# CPU.net
KiCad netlist of a schematic drawn in Altium Designer
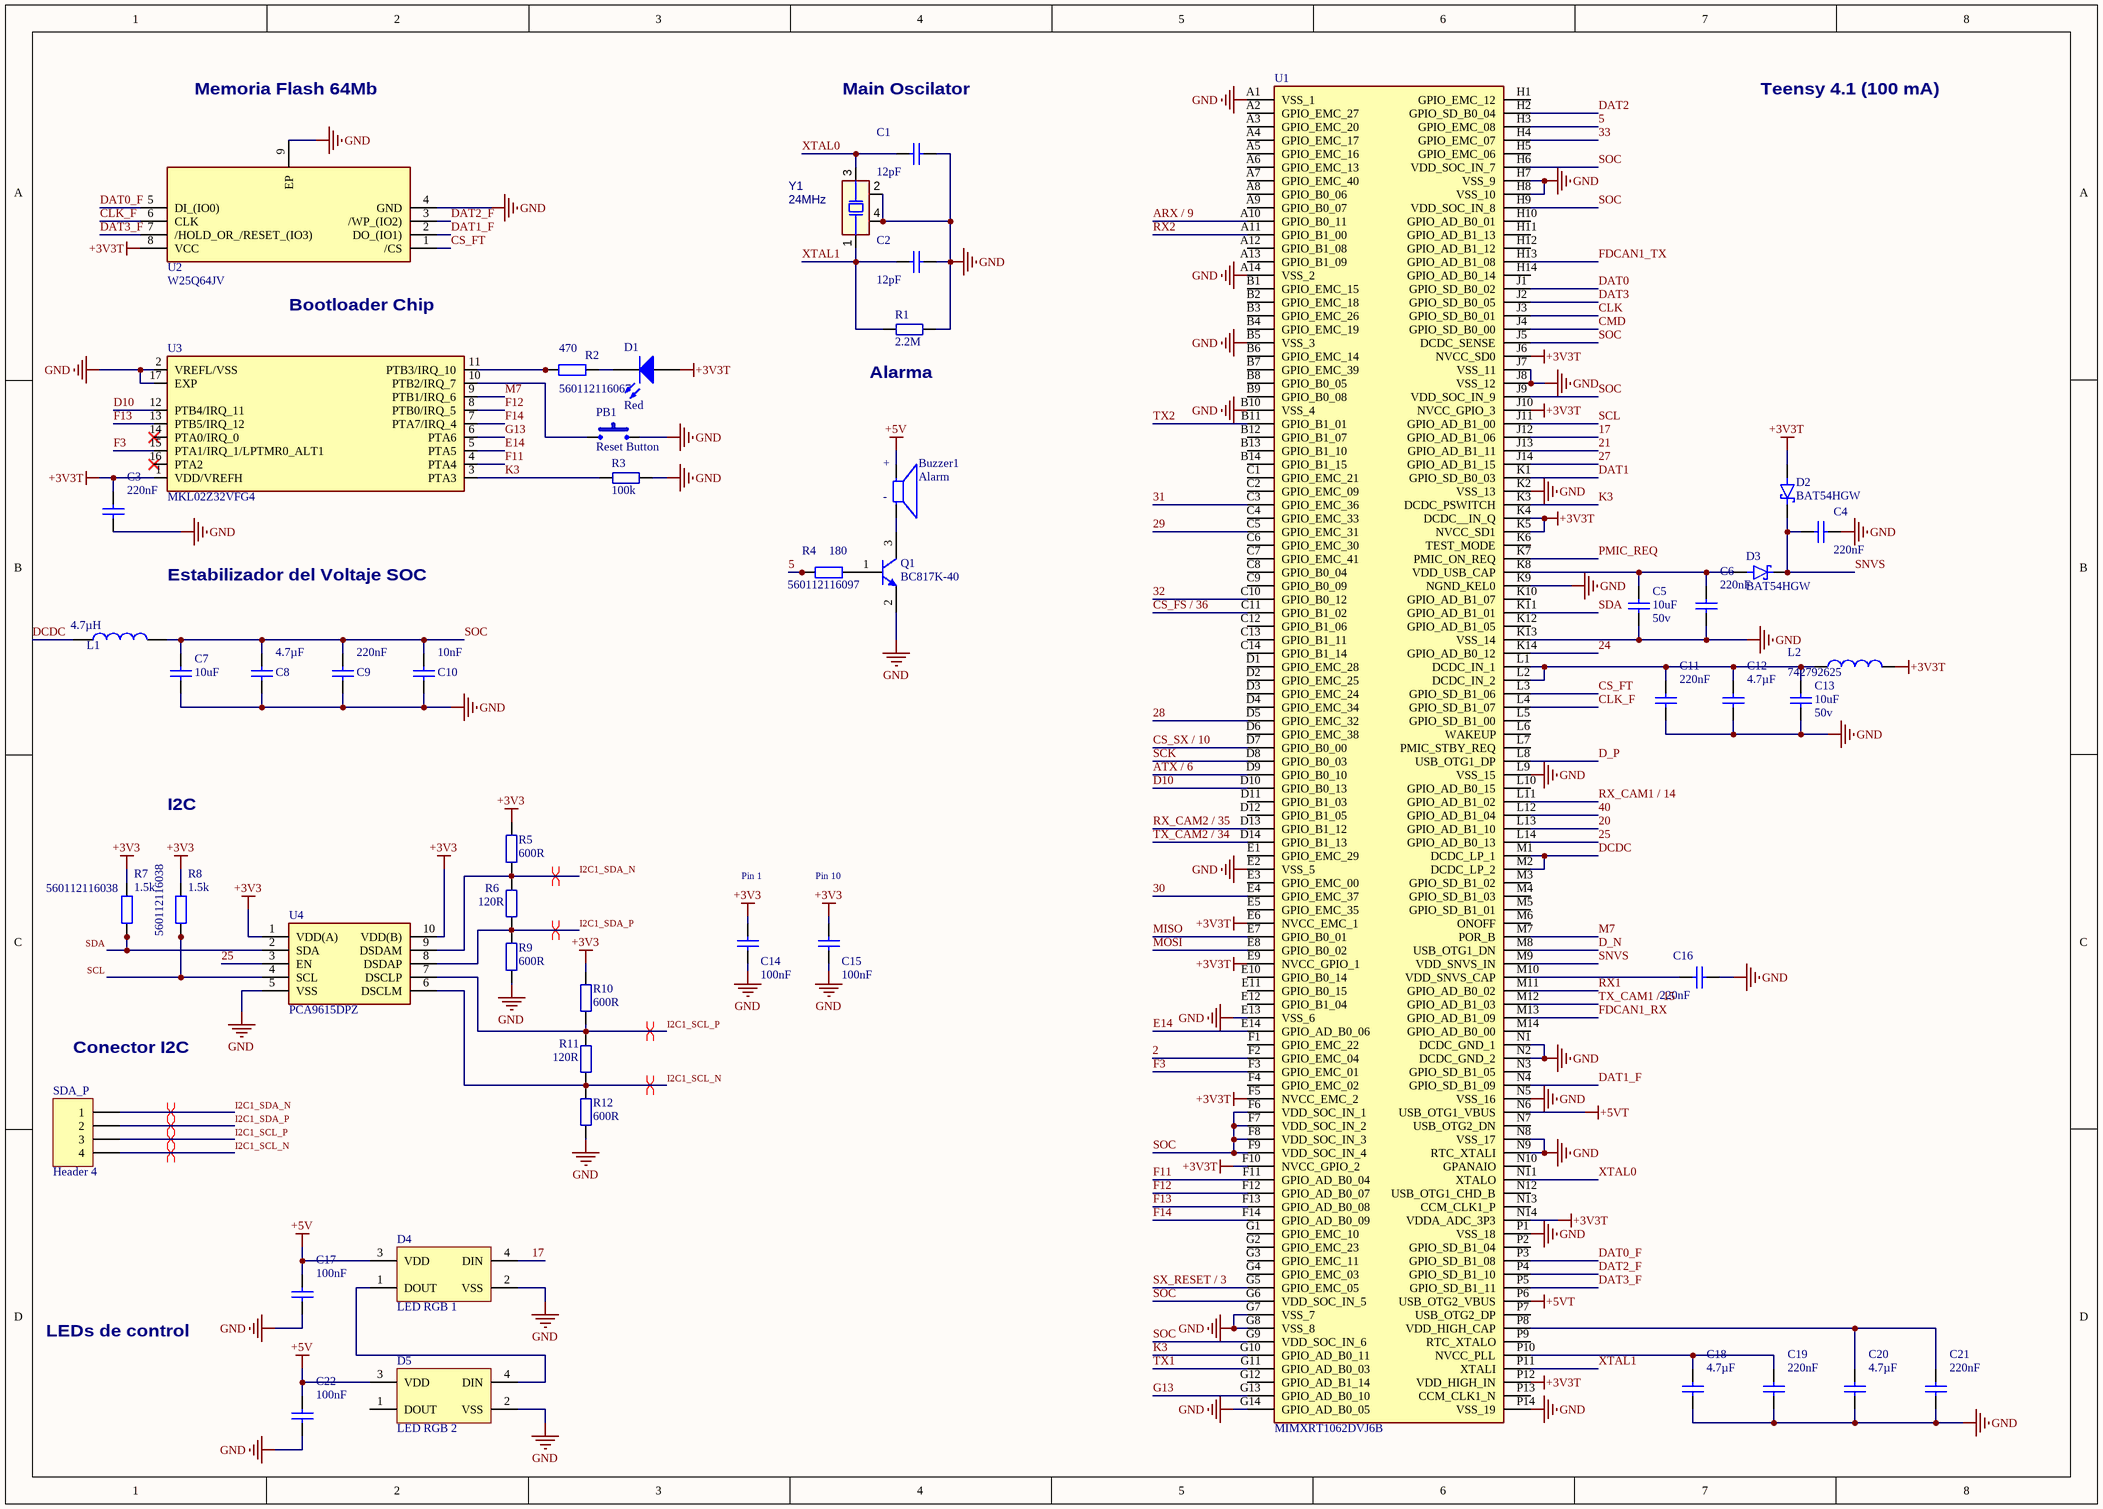
[diagram p0:  CPU.SchDoc]

(export (version "E")
  (design (tool "Eeschema 10.0.6"))
  (components
    (comp (ref "Buzzer1")
      (value "Alarm")
      (footprint "CMT-8504-100-SMT-TR-Footprint-1")
      (libsource (lib "LEEM UPM") (part "CMT-8504-100"))
    )
    (comp (ref "C1")
      (value "12pF")
      (footprint "WCAP-CSRF_0402")
      (description "WCAP-CSRF Multilayer Ceramic Chip Capacitor High Frequency, size 0402, NP0 Class I, 12pF, 50VDC")
      (fields
        (field (name "MANUFACTURER PART NUMBER") "885392005127")
        (field (name "MANUFACTURER") "Wurth Elektronik")
      )
      (libsource (lib "LEEM UPM") (part "885392005147"))
    )
    (comp (ref "C2")
      (value "12pF")
      (footprint "WCAP-CSRF_0402")
      (description "WCAP-CSRF Multilayer Ceramic Chip Capacitor High Frequency, size 0402, NP0 Class I, 12pF, 50VDC")
      (fields
        (field (name "MANUFACTURER PART NUMBER") "885392005127")
        (field (name "MANUFACTURER") "Wurth Elektronik")
      )
      (libsource (lib "LEEM UPM") (part "885392005147"))
    )
    (comp (ref "C3")
      (value "220nF")
      (footprint "WCAP-CSGP_0603_L1.6W0.8H0.8_Reflow")
      (description "WCAP-CSGP Multilayer Ceramic Chip Capacitor, General Purpose, size 0603, X7R, 220nF, 25VDC")
      (fields
        (field (name "MANUFACTURER PART NUMBER") "885012206073")
        (field (name "MANUFACTURER") "Wurth Elektronik")
      )
      (libsource (lib "LEEM UPM") (part "885012209047R"))
    )
    (comp (ref "C4")
      (value "220nF")
      (footprint "WCAP-CSGP_0603_L1.6W0.8H0.8_Reflow")
      (description "WCAP-CSGP Multilayer Ceramic Chip Capacitor, General Purpose, size 0603, X7R, 220nF, 25VDC")
      (fields
        (field (name "MANUFACTURER PART NUMBER") "885012206073")
        (field (name "MANUFACTURER") "Wurth Elektronik")
      )
      (libsource (lib "LEEM UPM") (part "885012209047R"))
    )
    (comp (ref "C5")
      (value "10uF")
      (footprint "MY_0603")
      (description "None polar capacitor")
      (fields
        (field (name "ASID PART NUMBER") "C-AS")
        (field (name "VOLTE") "50v")
        (field (name "Comment") "Cap ceramic")
      )
      (libsource (lib "LEEM UPM") (part "Cap ceramic"))
    )
    (comp (ref "C6")
      (value "220nF")
      (footprint "WCAP-CSGP_0603_L1.6W0.8H0.8_Reflow")
      (description "WCAP-CSGP Multilayer Ceramic Chip Capacitor, General Purpose, size 0603, X7R, 220nF, 25VDC")
      (fields
        (field (name "MANUFACTURER PART NUMBER") "885012206073")
        (field (name "MANUFACTURER") "Wurth Elektronik")
      )
      (libsource (lib "LEEM UPM") (part "885012209047R"))
    )
    (comp (ref "C7")
      (value "10uF")
      (footprint "MY_0603")
      (description "None polar capacitor")
      (fields (field (name "ASID PART NUMBER") "C-AS") (field (name "Comment") "Cap ceramic"))
      (libsource (lib "LEEM UPM") (part "Cap ceramic"))
    )
    (comp (ref "C8")
      (value "4.7µF")
      (footprint "WCAP-CSGP_0603_L1.6W0.8H0.8_Reflow")
      (description "WCAP-CSGP Multilayer Ceramic Chip Capacitor, General Purpose, size 0603, X5R, 4.7uF, 10VDC")
      (fields
        (field (name "MANUFACTURER PART NUMBER") "885012106012")
        (field (name "MANUFACTURER") "Wurth Elektronik")
      )
      (libsource (lib "LEEM UPM") (part "885012209047R"))
    )
    (comp (ref "C9")
      (value "220nF")
      (footprint "WCAP-CSGP_0603_L1.6W0.8H0.8_Reflow")
      (description "WCAP-CSGP Multilayer Ceramic Chip Capacitor, General Purpose, size 0603, X7R, 220nF, 25VDC")
      (fields
        (field (name "MANUFACTURER PART NUMBER") "885012206073")
        (field (name "MANUFACTURER") "Wurth Elektronik")
      )
      (libsource (lib "LEEM UPM") (part "885012209047R"))
    )
    (comp (ref "C10")
      (value "10nF")
      (footprint "WCAP-CSGP_0603_L1.6W0.8H0.8_Reflow")
      (description "WCAP-CSGP Multilayer Ceramic Chip Capacitor, General Purpose, size 0603, X7R, 10nF, 25VDC")
      (fields
        (field (name "MANUFACTURER") "Wurth Elektronik")
        (field (name "MANUFACTURER PART NUMBER") "885012206065")
      )
      (libsource (lib "LEEM UPM") (part "885012209047R"))
    )
    (comp (ref "C11")
      (value "220nF")
      (footprint "WCAP-CSGP_0603_L1.6W0.8H0.8_Reflow")
      (description "WCAP-CSGP Multilayer Ceramic Chip Capacitor, General Purpose, size 0603, X7R, 220nF, 25VDC")
      (fields
        (field (name "MANUFACTURER PART NUMBER") "885012206073")
        (field (name "MANUFACTURER") "Wurth Elektronik")
      )
      (libsource (lib "LEEM UPM") (part "885012209047R"))
    )
    (comp (ref "C12")
      (value "4.7µF")
      (footprint "WCAP-CSGP_0603_L1.6W0.8H0.8_Reflow")
      (description "WCAP-CSGP Multilayer Ceramic Chip Capacitor, General Purpose, size 0603, X5R, 4.7uF, 10VDC")
      (fields
        (field (name "MANUFACTURER PART NUMBER") "885012106012")
        (field (name "MANUFACTURER") "Wurth Elektronik")
      )
      (libsource (lib "LEEM UPM") (part "885012209047R"))
    )
    (comp (ref "C13")
      (value "10uF")
      (footprint "MY_0603")
      (description "None polar capacitor")
      (fields
        (field (name "ASID PART NUMBER") "C-AS")
        (field (name "VOLTE") "50v")
        (field (name "Comment") "Cap ceramic")
      )
      (libsource (lib "LEEM UPM") (part "Cap ceramic"))
    )
    (comp (ref "C14")
      (value "100nF")
      (footprint "WCAP-CSGP_0603_L1.6W0.8H0.8_Reflow")
      (description "WCAP-CSGP Multilayer Ceramic Chip Capacitor, General Purpose, size 0603, X7R, 100nF, 25VDC")
      (fields
        (field (name "MANUFACTURER") "Wurth Elektronik")
        (field (name "MANUFACTURER PART NUMBER") "885012206071")
      )
      (libsource (lib "LEEM UPM") (part "885012209047R"))
    )
    (comp (ref "C15")
      (value "100nF")
      (footprint "WCAP-CSGP_0603_L1.6W0.8H0.8_Reflow")
      (description "WCAP-CSGP Multilayer Ceramic Chip Capacitor, General Purpose, size 0603, X7R, 100nF, 25VDC")
      (fields
        (field (name "MANUFACTURER") "Wurth Elektronik")
        (field (name "MANUFACTURER PART NUMBER") "885012206071")
      )
      (libsource (lib "LEEM UPM") (part "885012209047R"))
    )
    (comp (ref "C16")
      (value "220nF")
      (footprint "WCAP-CSGP_0603_L1.6W0.8H0.8_Reflow")
      (description "WCAP-CSGP Multilayer Ceramic Chip Capacitor, General Purpose, size 0603, X7R, 220nF, 25VDC")
      (fields
        (field (name "MANUFACTURER PART NUMBER") "885012206073")
        (field (name "MANUFACTURER") "Wurth Elektronik")
      )
      (libsource (lib "LEEM UPM") (part "885012209047R"))
    )
    (comp (ref "C17")
      (value "100nF")
      (footprint "WCAP-CSGP_0603_L1.6W0.8H0.8_Reflow")
      (description "WCAP-CSGP Multilayer Ceramic Chip Capacitor, General Purpose, size 0603, X7R, 100nF, 25VDC")
      (fields
        (field (name "MANUFACTURER") "Wurth Elektronik")
        (field (name "MANUFACTURER PART NUMBER") "885012206071")
      )
      (libsource (lib "LEEM UPM") (part "885012209047R"))
    )
    (comp (ref "C18")
      (value "4.7µF")
      (footprint "WCAP-CSGP_0603_L1.6W0.8H0.8_Reflow")
      (description "WCAP-CSGP Multilayer Ceramic Chip Capacitor, General Purpose, size 0603, X5R, 4.7uF, 10VDC")
      (fields
        (field (name "MANUFACTURER PART NUMBER") "885012106012")
        (field (name "MANUFACTURER") "Wurth Elektronik")
      )
      (libsource (lib "LEEM UPM") (part "885012209047R"))
    )
    (comp (ref "C19")
      (value "220nF")
      (footprint "WCAP-CSGP_0603_L1.6W0.8H0.8_Reflow")
      (description "WCAP-CSGP Multilayer Ceramic Chip Capacitor, General Purpose, size 0603, X7R, 220nF, 25VDC")
      (fields
        (field (name "MANUFACTURER PART NUMBER") "885012206073")
        (field (name "MANUFACTURER") "Wurth Elektronik")
      )
      (libsource (lib "LEEM UPM") (part "885012209047R"))
    )
    (comp (ref "C20")
      (value "4.7µF")
      (footprint "WCAP-CSGP_0603_L1.6W0.8H0.8_Reflow")
      (description "WCAP-CSGP Multilayer Ceramic Chip Capacitor, General Purpose, size 0603, X5R, 4.7uF, 10VDC")
      (fields
        (field (name "MANUFACTURER PART NUMBER") "885012106012")
        (field (name "MANUFACTURER") "Wurth Elektronik")
      )
      (libsource (lib "LEEM UPM") (part "885012209047R"))
    )
    (comp (ref "C21")
      (value "220nF")
      (footprint "WCAP-CSGP_0603_L1.6W0.8H0.8_Reflow")
      (description "WCAP-CSGP Multilayer Ceramic Chip Capacitor, General Purpose, size 0603, X7R, 220nF, 25VDC")
      (fields
        (field (name "MANUFACTURER PART NUMBER") "885012206073")
        (field (name "MANUFACTURER") "Wurth Elektronik")
      )
      (libsource (lib "LEEM UPM") (part "885012209047R"))
    )
    (comp (ref "C22")
      (value "100nF")
      (footprint "WCAP-CSGP_0603_L1.6W0.8H0.8_Reflow")
      (description "WCAP-CSGP Multilayer Ceramic Chip Capacitor, General Purpose, size 0603, X7R, 100nF, 25VDC")
      (fields
        (field (name "MANUFACTURER") "Wurth Elektronik")
        (field (name "MANUFACTURER PART NUMBER") "885012206071")
      )
      (libsource (lib "LEEM UPM") (part "885012209047R"))
    )
    (comp (ref "D1")
      (value "Red")
      (footprint "MY_LED_0805")
      (description "Typical INFRARED GaAs LED")
      (fields (field (name "ASID PART NUMBER") "LED-AS"))
      (libsource (lib "Mylib+Rev+4") (part "LED"))
    )
    (comp (ref "D2")
      (value "BAT54HGW")
      (footprint "BAT54HGW-Footprint-1")
      (description "BAT54HGW Schotty Diode")
      (libsource (lib "LEEM UPM") (part "BAT54HGW"))
    )
    (comp (ref "D3")
      (value "BAT54HGW")
      (footprint "BAT54HGW-Footprint-1")
      (description "BAT54HGW Schotty Diode")
      (libsource (lib "LEEM UPM") (part "BAT54HGW"))
    )
    (comp (ref "D4")
      (value "LED RGB 1")
      (footprint "1313210530000")
      (description "WL-ICLED Integrated Controller within LED, Side View 3210, 5.5mA")
      (fields
        (field (name "MANUFACTURER") "Wurth Elektronik")
        (field (name "MANUFACTURER PART NUMBER") "1313210530000")
      )
      (libsource (lib "LEEM UPM") (part "1313210530000"))
    )
    (comp (ref "D5")
      (value "LED RGB 2")
      (footprint "1313210530000")
      (description "WL-ICLED Integrated Controller within LED, Side View 3210, 5.5mA")
      (fields
        (field (name "MANUFACTURER") "Wurth Elektronik")
        (field (name "MANUFACTURER PART NUMBER") "1313210530000")
      )
      (libsource (lib "LEEM UPM") (part "1313210530000"))
    )
    (comp (ref "L1")
      (value "74479775247")
      (footprint "WE-PMI_0805_L2W1.2H1")
      (description "WE-PMI SMT Power Multilayer Inductor, size 0805, 4.7µH, 0.85A, 312.5mO")
      (fields (field (name "INDUCTANCE") "4.7µH") (field (name "MANUFACTURER") "Wurth Elektronik"))
      (libsource (lib "LEEM UPM") (part "74479887310A"))
    )
    (comp (ref "L2")
      (value "742792625")
      (footprint "WE-CBF_0603_L1.6W0.8H0.8_HC")
      (description "WE-CBF SMT EMI Suppression Ferrite Bead, size 0603, 120Ohm, 2A")
      (fields (field (name "MANUFACTURER") "Wurth Elektronik"))
      (libsource (lib "LEEM UPM") (part "7427928801"))
    )
    (comp (ref "PB1")
      (value "Reset Button")
      (footprint "Push Button-Footprint-1")
      (description "Push Button")
      (fields (field (name "SOURCE") "IFS_Altium.SchLib"))
      (libsource (lib "LEEM UPM") (part "Push Button"))
    )
    (comp (ref "Q1")
      (value "BC817K-40")
      (footprint "INF-SOT23_N")
      (description "Trans GP BJT NPN 45V 0.5A 500mW Automotive 3-Pin SOT-23 T/R")
      (libsource (lib "LEEM UPM") (part "INF-BJTNPN-BEC-3"))
    )
    (comp (ref "R1")
      (value "2.2M")
      (footprint "R0603-0.45")
      (description "Resistor, generic")
      (libsource (lib "IFS_Altium") (part "R"))
    )
    (comp (ref "R2")
      (value "560112116067")
      (footprint "WRIS-RSKS_0603_Reflow")
      (description "WRIS-RSKS Thick Film Resistor, size 0603, 470Ohm, 100mW")
      (fields (field (name "MANUFACTURER") "Wurth Elektronik") (field (name "ALTIUM_VALUE") "470"))
      (libsource (lib "LEEM UPM") (part "560112140010"))
    )
    (comp (ref "R3")
      (value "100k")
      (footprint "R0603-0.45")
      (description "Resistor, generic")
      (libsource (lib "IFS_Altium") (part "R"))
    )
    (comp (ref "R4")
      (value "560112116097")
      (footprint "WRIS-RSKS_0603_Reflow")
      (description "WRIS-RSKS Thick Film Resistor, size 0603, 180Ohm, 100mW")
      (fields (field (name "ALTIUM_VALUE") "180") (field (name "MANUFACTURER") "Wurth Elektronik"))
      (libsource (lib "") (part "560112140010_2"))
    )
    (comp (ref "R5")
      (value "600R")
      (footprint "R0603-0.45")
      (description "Resistor, 600R, 0805, 0.5W")
      (fields
        (field (name "MANUFACTURER") "Vishay")
        (field (name "MANUFACTURER PART NUMBER") "CRCW0805600RFKEAHP")
      )
      (libsource (lib "LEEM UPM") (part "RK73H2ALTD1004F"))
    )
    (comp (ref "R6")
      (value "120R")
      (footprint "R0603-0.45")
      (description "Resistor, 120R, 0805, 0.5W")
      (fields
        (field (name "MANUFACTURER") "Panasonic")
        (field (name "MANUFACTURER PART NUMBER") "ERJ-P06F1200V")
      )
      (libsource (lib "LEEM UPM") (part "RK73H2ALTD1004F"))
    )
    (comp (ref "R7")
      (value "560112116038")
      (footprint "WRIS-RSKS_0603_Reflow")
      (description "WRIS-RSKS Thick Film Resistor, size 0603, 1500Ohm, 100mW")
      (fields (field (name "ALTIUM_VALUE") "1.5k") (field (name "MANUFACTURER") "Wurth Elektronik"))
      (libsource (lib "") (part "560112140010_1"))
    )
    (comp (ref "R8")
      (value "560112116038")
      (footprint "WRIS-RSKS_0603_Reflow")
      (description "WRIS-RSKS Thick Film Resistor, size 0603, 1500Ohm, 100mW")
      (fields (field (name "ALTIUM_VALUE") "1.5k") (field (name "MANUFACTURER") "Wurth Elektronik"))
      (libsource (lib "") (part "560112140010_1"))
    )
    (comp (ref "R9")
      (value "600R")
      (footprint "R0603-0.45")
      (description "Resistor, 600R, 0805, 0.5W")
      (fields
        (field (name "MANUFACTURER") "Vishay")
        (field (name "MANUFACTURER PART NUMBER") "CRCW0805600RFKEAHP")
      )
      (libsource (lib "LEEM UPM") (part "RK73H2ALTD1004F"))
    )
    (comp (ref "R10")
      (value "600R")
      (footprint "R0603-0.45")
      (description "Resistor, 600R, 0805, 0.5W")
      (fields
        (field (name "MANUFACTURER") "Vishay")
        (field (name "MANUFACTURER PART NUMBER") "CRCW0805600RFKEAHP")
      )
      (libsource (lib "LEEM UPM") (part "RK73H2ALTD1004F"))
    )
    (comp (ref "R11")
      (value "120R")
      (footprint "R0603-0.45")
      (description "Resistor, generic")
      (fields
        (field (name "MANUFACTURER") "Panasonic")
        (field (name "MANUFACTURER PART NUMBER") "ERJ-P06F1200V")
      )
      (libsource (lib "LEEM UPM") (part "RK73H2ALTD1004F"))
    )
    (comp (ref "R12")
      (value "600R")
      (footprint "R0603-0.45")
      (description "Resistor, 600R, 0805, 0.5W")
      (fields
        (field (name "MANUFACTURER") "Vishay")
        (field (name "MANUFACTURER PART NUMBER") "CRCW0805600RFKEAHP")
      )
      (libsource (lib "LEEM UPM") (part "RK73H2ALTD1004F"))
    )
    (comp (ref "SDA_P")
      (value "Header 4")
      (footprint "JST XH")
      (description "Header, 4-Pin")
      (fields (field (name "ASID PART NUMBER") "Header 4-AS"))
      (libsource (lib "LEEM UPM") (part "Header 4"))
    )
    (comp (ref "U1")
      (value "MIMXRT1062DVJ6B")
      (footprint "BGA196C80P14X14_1200X1200X152")
      (description "IC MCU 32BIT EXT MEM 196MAPBGA")
      (fields (field (name "MOUSER PART NUMBER") "771-MIMXRT1062DVJ6B"))
      (libsource (lib "LEEM UPM") (part "MIMXRT1062DVJ6B"))
    )
    (comp (ref "U2")
      (value "W25Q64JV")
      (footprint "WSON 8X6")
      (description "NOR Flash spiFlash, 64M-bit, DTR, 4Kb Uniform Sector")
      (fields
        (field (name "ARROW PART NUMBER") "W25Q64JVXGIM TR")
        (field (name "MOUSER PART NUMBER") "454-W25Q64JVXGIMTR")
      )
      (libsource (lib "LEEM UPM") (part "W25Q64JV"))
    )
    (comp (ref "U3")
      (value "MKL02Z32VFG4")
      (footprint "QFN50P300X300X65-17N")
      (description "ARMÂ®CortexÂ®-M0+ Kinetis KL02å¾®æŽ§åˆ¶å™¨IC 32ä½48MHz 32KBï¼ˆ32K x 8ï¼‰é—ªå­˜16-QFNï¼ˆ3x3ï¼‰")
      (fields (field (name "MF") "NXP USA"))
      (libsource (lib "LEEM UPM") (part "MKL02Z32VFG4"))
    )
    (comp (ref "U4")
      (value "PCA9615DPZ")
      (footprint "PCA9615DPZ-Footprint-1")
      (description "2 Channel  I2C-busbuffer")
      (fields (field (name "MANUFACTURER") "NXP Semiconductors"))
      (libsource (lib "LEEM UPM") (part "PCA9615DPZ-Symbol-1"))
    )
    (comp (ref "Y1")
      (value "24MHz")
      (footprint "EPSON-FA-128_V")
      (description "Crystal, 24 MHz, +/- 10 ppm, -20 to 75 degC, 4-Pin SMD, RoHS, Tape and Reel")
      (libsource (lib "LEEM UPM") (part "CMP-00014-7"))
    )
  )
  (nets
    (net (code "1") (name "+3V3") (class "Default")
      (node (ref "C14") (pin "2") (pinfunction "2_2") (pintype "passive"))
      (node (ref "C15") (pin "2") (pinfunction "2_2") (pintype "passive"))
      (node (ref "R10") (pin "1") (pinfunction "1_1") (pintype "passive"))
      (node (ref "R5") (pin "1") (pinfunction "1_1") (pintype "passive"))
      (node (ref "R7") (pin "1") (pinfunction "1_1") (pintype "passive"))
      (node (ref "R8") (pin "1") (pinfunction "1_1") (pintype "passive"))
      (node (ref "U4") (pin "1") (pinfunction "VDD(A)_1") (pintype "passive"))
      (node (ref "U4") (pin "10") (pinfunction "VDD(B)_10") (pintype "passive"))
    )
    (net (code "2") (name "+3V3T") (class "Default")
      (node (ref "C3") (pin "1") (pinfunction "1_1") (pintype "passive"))
      (node (ref "D1") (pin "A") (pinfunction "A_A") (pintype "passive"))
      (node (ref "D2") (pin "A") (pinfunction "A_A") (pintype "passive"))
      (node (ref "L2") (pin "2") (pinfunction "2_2") (pintype "passive"))
      (node (ref "U1") (pin "E6") (pinfunction "NVCC_EMC_1_E6") (pintype "passive"))
      (node (ref "U1") (pin "E9") (pinfunction "NVCC_GPIO_1_E9") (pintype "passive"))
      (node (ref "U1") (pin "F10") (pinfunction "NVCC_GPIO_2_F10") (pintype "passive"))
      (node (ref "U1") (pin "F5") (pinfunction "NVCC_EMC_2_F5") (pintype "passive"))
      (node (ref "U1") (pin "J10") (pinfunction "NVCC_GPIO_3_J10") (pintype "passive"))
      (node (ref "U1") (pin "J6") (pinfunction "NVCC_SD0_J6") (pintype "passive"))
      (node (ref "U1") (pin "K4") (pinfunction "DCDC__IN_Q_K4") (pintype "passive"))
      (node (ref "U1") (pin "K5") (pinfunction "NVCC_SD1_K5") (pintype "passive"))
      (node (ref "U1") (pin "N14") (pinfunction "VDDA_ADC_3P3_N14") (pintype "passive"))
      (node (ref "U1") (pin "P12") (pinfunction "VDD_HIGH_IN_P12") (pintype "passive"))
      (node (ref "U2") (pin "8") (pinfunction "VCC_8") (pintype "passive"))
      (node (ref "U3") (pin "1") (pinfunction "VDD/VREFH_1") (pintype "power_in"))
    )
    (net (code "3") (name "+5V") (class "Default")
      (node (ref "Buzzer1") (pin "P") (pinfunction "P_P") (pintype "passive"))
      (node (ref "C17") (pin "1") (pinfunction "1_1") (pintype "passive"))
      (node (ref "C22") (pin "1") (pinfunction "1_1") (pintype "passive"))
      (node (ref "D4") (pin "3") (pinfunction "VDD_3") (pintype "passive"))
      (node (ref "D5") (pin "3") (pinfunction "VDD_3") (pintype "passive"))
    )
    (net (code "4") (name "+5VT") (class "Default")
      (node (ref "U1") (pin "N6") (pinfunction "USB_OTG1_VBUS_N6") (pintype "passive"))
      (node (ref "U1") (pin "P6") (pinfunction "USB_OTG2_VBUS_P6") (pintype "passive"))
    )
    (net (code "5") (name "/2") (class "Default")
      (node (ref "U1") (pin "F2") (pinfunction "GPIO_EMC_04_F2") (pintype "passive"))
    )
    (net (code "6") (name "/5") (class "Default")
      (node (ref "R4") (pin "1") (pinfunction "1_1") (pintype "passive"))
      (node (ref "U1") (pin "H3") (pinfunction "GPIO_EMC_08_H3") (pintype "passive"))
    )
    (net (code "7") (name "/17") (class "Default")
      (node (ref "D4") (pin "4") (pinfunction "DIN_4") (pintype "passive"))
      (node (ref "U1") (pin "J12") (pinfunction "GPIO_AD_B1_06_J12") (pintype "passive"))
    )
    (net (code "8") (name "/20") (class "Default")
      (node (ref "U1") (pin "L13") (pinfunction "GPIO_AD_B1_10_L13") (pintype "passive"))
    )
    (net (code "9") (name "/21") (class "Default")
      (node (ref "U1") (pin "J13") (pinfunction "GPIO_AD_B1_11_J13") (pintype "passive"))
    )
    (net (code "10") (name "/24") (class "Default")
      (node (ref "U1") (pin "K14") (pinfunction "GPIO_AD_B0_12_K14") (pintype "passive"))
    )
    (net (code "11") (name "/25") (class "Default")
      (node (ref "U1") (pin "L14") (pinfunction "GPIO_AD_B0_13_L14") (pintype "passive"))
      (node (ref "U4") (pin "3") (pinfunction "EN_3") (pintype "passive"))
    )
    (net (code "12") (name "/27") (class "Default")
      (node (ref "U1") (pin "J14") (pinfunction "GPIO_AD_B1_15_J14") (pintype "passive"))
    )
    (net (code "13") (name "/28") (class "Default")
      (node (ref "U1") (pin "D5") (pinfunction "GPIO_EMC_32_D5") (pintype "passive"))
    )
    (net (code "14") (name "/29") (class "Default")
      (node (ref "U1") (pin "C5") (pinfunction "GPIO_EMC_31_C5") (pintype "passive"))
    )
    (net (code "15") (name "/30") (class "Default")
      (node (ref "U1") (pin "E4") (pinfunction "GPIO_EMC_37_E4") (pintype "passive"))
    )
    (net (code "16") (name "/31") (class "Default")
      (node (ref "U1") (pin "C3") (pinfunction "GPIO_EMC_36_C3") (pintype "passive"))
    )
    (net (code "17") (name "/32") (class "Default")
      (node (ref "U1") (pin "C10") (pinfunction "GPIO_B0_12_C10") (pintype "passive"))
    )
    (net (code "18") (name "/33") (class "Default")
      (node (ref "U1") (pin "H4") (pinfunction "GPIO_EMC_07_H4") (pintype "passive"))
    )
    (net (code "19") (name "/40") (class "Default")
      (node (ref "U1") (pin "L12") (pinfunction "GPIO_AD_B1_04_L12") (pintype "passive"))
    )
    (net (code "20") (name "/ARX {slash} 9") (class "Default")
      (node (ref "U1") (pin "A10") (pinfunction "GPIO_B0_11_A10") (pintype "passive"))
    )
    (net (code "21") (name "/ATX {slash} 6") (class "Default")
      (node (ref "U1") (pin "D9") (pinfunction "GPIO_B0_10_D9") (pintype "passive"))
    )
    (net (code "22") (name "/CLK") (class "Default")
      (node (ref "U1") (pin "J3") (pinfunction "GPIO_SD_B0_01_J3") (pintype "passive"))
    )
    (net (code "23") (name "/CLK_F") (class "Default")
      (node (ref "U1") (pin "L4") (pinfunction "GPIO_SD_B1_07_L4") (pintype "passive"))
      (node (ref "U2") (pin "6") (pinfunction "CLK_6") (pintype "passive"))
    )
    (net (code "24") (name "/CMD") (class "Default")
      (node (ref "U1") (pin "J4") (pinfunction "GPIO_SD_B0_00_J4") (pintype "passive"))
    )
    (net (code "25") (name "/CS_FS {slash} 36") (class "Default")
      (node (ref "U1") (pin "C11") (pinfunction "GPIO_B1_02_C11") (pintype "passive"))
    )
    (net (code "26") (name "/CS_FT") (class "Default")
      (node (ref "U1") (pin "L3") (pinfunction "GPIO_SD_B1_06_L3") (pintype "passive"))
      (node (ref "U2") (pin "1") (pinfunction "/CS_1") (pintype "passive"))
    )
    (net (code "27") (name "/CS_SX {slash} 10") (class "Default")
      (node (ref "U1") (pin "D7") (pinfunction "GPIO_B0_00_D7") (pintype "passive"))
    )
    (net (code "28") (name "/D10") (class "Default")
      (node (ref "U1") (pin "D10") (pinfunction "GPIO_B0_13_D10") (pintype "passive"))
      (node (ref "U3") (pin "12") (pinfunction "PTB4/IRQ_11_12") (pintype "bidirectional"))
    )
    (net (code "29") (name "/DAT0") (class "Default")
      (node (ref "U1") (pin "J1") (pinfunction "GPIO_SD_B0_02_J1") (pintype "passive"))
    )
    (net (code "30") (name "/DAT0_F") (class "Default")
      (node (ref "U1") (pin "P3") (pinfunction "GPIO_SD_B1_08_P3") (pintype "passive"))
      (node (ref "U2") (pin "5") (pinfunction "DI_(IO0)_5") (pintype "passive"))
    )
    (net (code "31") (name "/DAT1") (class "Default")
      (node (ref "U1") (pin "K1") (pinfunction "GPIO_SD_B0_03_K1") (pintype "passive"))
    )
    (net (code "32") (name "/DAT1_F") (class "Default")
      (node (ref "U1") (pin "N4") (pinfunction "GPIO_SD_B1_09_N4") (pintype "passive"))
      (node (ref "U2") (pin "2") (pinfunction "DO_(IO1)_2") (pintype "passive"))
    )
    (net (code "33") (name "/DAT2") (class "Default")
      (node (ref "U1") (pin "H2") (pinfunction "GPIO_SD_B0_04_H2") (pintype "passive"))
    )
    (net (code "34") (name "/DAT2_F") (class "Default")
      (node (ref "U1") (pin "P4") (pinfunction "GPIO_SD_B1_10_P4") (pintype "passive"))
      (node (ref "U2") (pin "3") (pinfunction "/WP_(IO2)_3") (pintype "passive"))
    )
    (net (code "35") (name "/DAT3") (class "Default")
      (node (ref "U1") (pin "J2") (pinfunction "GPIO_SD_B0_05_J2") (pintype "passive"))
    )
    (net (code "36") (name "/DAT3_F") (class "Default")
      (node (ref "U1") (pin "P5") (pinfunction "GPIO_SD_B1_11_P5") (pintype "passive"))
      (node (ref "U2") (pin "7") (pinfunction "/HOLD_OR_/RESET_(IO3)_7") (pintype "passive"))
    )
    (net (code "37") (name "/DCDC") (class "Default")
      (node (ref "L1") (pin "1") (pinfunction "1_1") (pintype "passive"))
      (node (ref "U1") (pin "M1") (pinfunction "DCDC_LP_1_M1") (pintype "passive"))
      (node (ref "U1") (pin "M2") (pinfunction "DCDC_LP_2_M2") (pintype "passive"))
    )
    (net (code "38") (name "/D_N") (class "Default")
      (node (ref "U1") (pin "M8") (pinfunction "USB_OTG1_DN_M8") (pintype "passive"))
    )
    (net (code "39") (name "/D_P") (class "Default")
      (node (ref "U1") (pin "L8") (pinfunction "USB_OTG1_DP_L8") (pintype "passive"))
    )
    (net (code "40") (name "/E14") (class "Default")
      (node (ref "U1") (pin "E14") (pinfunction "GPIO_AD_B0_06_E14") (pintype "passive"))
      (node (ref "U3") (pin "5") (pinfunction "PTA5_5") (pintype "bidirectional"))
    )
    (net (code "41") (name "/F3") (class "Default")
      (node (ref "U1") (pin "F3") (pinfunction "GPIO_EMC_01_F3") (pintype "passive"))
      (node (ref "U3") (pin "15") (pinfunction "PTA1/IRQ_1/LPTMR0_ALT1_15") (pintype "bidirectional"))
    )
    (net (code "42") (name "/F11") (class "Default")
      (node (ref "U1") (pin "F11") (pinfunction "GPIO_AD_B0_04_F11") (pintype "passive"))
      (node (ref "U3") (pin "4") (pinfunction "PTA4_4") (pintype "bidirectional"))
    )
    (net (code "43") (name "/F12") (class "Default")
      (node (ref "U1") (pin "F12") (pinfunction "GPIO_AD_B0_07_F12") (pintype "passive"))
      (node (ref "U3") (pin "8") (pinfunction "PTB0/IRQ_5_8") (pintype "bidirectional"))
    )
    (net (code "44") (name "/F13") (class "Default")
      (node (ref "U1") (pin "F13") (pinfunction "GPIO_AD_B0_08_F13") (pintype "passive"))
      (node (ref "U3") (pin "13") (pinfunction "PTB5/IRQ_12_13") (pintype "bidirectional"))
    )
    (net (code "45") (name "/F14") (class "Default")
      (node (ref "U1") (pin "F14") (pinfunction "GPIO_AD_B0_09_F14") (pintype "passive"))
      (node (ref "U3") (pin "7") (pinfunction "PTA7/IRQ_4_7") (pintype "bidirectional"))
    )
    (net (code "46") (name "/FDCAN1_RX") (class "Default")
      (node (ref "U1") (pin "M13") (pinfunction "GPIO_AD_B1_09_M13") (pintype "passive"))
    )
    (net (code "47") (name "/FDCAN1_TX") (class "Default")
      (node (ref "U1") (pin "H13") (pinfunction "GPIO_AD_B1_08_H13") (pintype "passive"))
    )
    (net (code "48") (name "/G13") (class "Default")
      (node (ref "U1") (pin "G13") (pinfunction "GPIO_AD_B0_10_G13") (pintype "passive"))
      (node (ref "U3") (pin "6") (pinfunction "PTA6_6") (pintype "bidirectional"))
    )
    (net (code "49") (name "/I2C1_SCL_N") (class "Default")
      (node (ref "R11") (pin "1") (pinfunction "1_1") (pintype "passive"))
      (node (ref "R12") (pin "1") (pinfunction "1_1") (pintype "passive"))
      (node (ref "SDA_P") (pin "4") (pinfunction "4_4") (pintype "passive"))
      (node (ref "U4") (pin "6") (pinfunction "DSCLM_6") (pintype "passive"))
    )
    (net (code "50") (name "/I2C1_SCL_P") (class "Default")
      (node (ref "R10") (pin "2") (pinfunction "2_2") (pintype "passive"))
      (node (ref "R11") (pin "2") (pinfunction "2_2") (pintype "passive"))
      (node (ref "SDA_P") (pin "3") (pinfunction "3_3") (pintype "passive"))
      (node (ref "U4") (pin "7") (pinfunction "DSCLP_7") (pintype "passive"))
    )
    (net (code "51") (name "/I2C1_SDA_N") (class "Default")
      (node (ref "R5") (pin "2") (pinfunction "2_2") (pintype "passive"))
      (node (ref "R6") (pin "2") (pinfunction "2_2") (pintype "passive"))
      (node (ref "SDA_P") (pin "1") (pinfunction "1_1") (pintype "passive"))
      (node (ref "U4") (pin "9") (pinfunction "DSDAM_9") (pintype "passive"))
    )
    (net (code "52") (name "/I2C1_SDA_P") (class "Default")
      (node (ref "R6") (pin "1") (pinfunction "1_1") (pintype "passive"))
      (node (ref "R9") (pin "1") (pinfunction "1_1") (pintype "passive"))
      (node (ref "SDA_P") (pin "2") (pinfunction "2_2") (pintype "passive"))
      (node (ref "U4") (pin "8") (pinfunction "DSDAP_8") (pintype "passive"))
    )
    (net (code "53") (name "/K3") (class "Default")
      (node (ref "R3") (pin "1") (pinfunction "1_1") (pintype "passive"))
      (node (ref "U1") (pin "G10") (pinfunction "GPIO_AD_B0_11_G10") (pintype "passive"))
      (node (ref "U1") (pin "K3") (pinfunction "DCDC_PSWITCH_K3") (pintype "passive"))
      (node (ref "U3") (pin "3") (pinfunction "PTA3_3") (pintype "bidirectional"))
    )
    (net (code "54") (name "/M7") (class "Default")
      (node (ref "U1") (pin "M7") (pinfunction "POR_B_M7") (pintype "passive"))
      (node (ref "U3") (pin "9") (pinfunction "PTB1/IRQ_6_9") (pintype "bidirectional"))
    )
    (net (code "55") (name "/MISO") (class "Default")
      (node (ref "U1") (pin "E7") (pinfunction "GPIO_B0_01_E7") (pintype "passive"))
    )
    (net (code "56") (name "/MOSI") (class "Default")
      (node (ref "U1") (pin "E8") (pinfunction "GPIO_B0_02_E8") (pintype "passive"))
    )
    (net (code "57") (name "/PMIC_REQ") (class "Default")
      (node (ref "U1") (pin "K7") (pinfunction "PMIC_ON_REQ_K7") (pintype "passive"))
    )
    (net (code "58") (name "/RX1") (class "Default")
      (node (ref "U1") (pin "M11") (pinfunction "GPIO_AD_B0_02_M11") (pintype "passive"))
    )
    (net (code "59") (name "/RX2") (class "Default")
      (node (ref "U1") (pin "A11") (pinfunction "GPIO_B1_00_A11") (pintype "passive"))
    )
    (net (code "60") (name "/RX_CAM1 {slash} 14") (class "Default")
      (node (ref "U1") (pin "L11") (pinfunction "GPIO_AD_B1_02_L11") (pintype "passive"))
    )
    (net (code "61") (name "/RX_CAM2 {slash} 35") (class "Default")
      (node (ref "U1") (pin "D13") (pinfunction "GPIO_B1_12_D13") (pintype "passive"))
    )
    (net (code "62") (name "/SCK") (class "Default")
      (node (ref "U1") (pin "D8") (pinfunction "GPIO_B0_03_D8") (pintype "passive"))
    )
    (net (code "63") (name "/SCL") (class "Default")
      (node (ref "R8") (pin "2") (pinfunction "2_2") (pintype "passive"))
      (node (ref "U1") (pin "J11") (pinfunction "GPIO_AD_B1_00_J11") (pintype "passive"))
      (node (ref "U4") (pin "4") (pinfunction "SCL_4") (pintype "passive"))
    )
    (net (code "64") (name "/SDA") (class "Default")
      (node (ref "R7") (pin "2") (pinfunction "2_2") (pintype "passive"))
      (node (ref "U1") (pin "K11") (pinfunction "GPIO_AD_B1_01_K11") (pintype "passive"))
      (node (ref "U4") (pin "2") (pinfunction "SDA_2") (pintype "passive"))
    )
    (net (code "65") (name "/SNVS") (class "Default")
      (node (ref "C4") (pin "2") (pinfunction "2_2") (pintype "passive"))
      (node (ref "D2") (pin "C") (pinfunction "K_C") (pintype "passive"))
      (node (ref "D3") (pin "C") (pinfunction "K_C") (pintype "passive"))
      (node (ref "U1") (pin "M9") (pinfunction "VDD_SNVS_IN_M9") (pintype "passive"))
    )
    (net (code "66") (name "/SOC") (class "Default")
      (node (ref "C10") (pin "1") (pinfunction "1_1") (pintype "passive"))
      (node (ref "C7") (pin "1") (pinfunction "1_1") (pintype "passive"))
      (node (ref "C8") (pin "1") (pinfunction "1_1") (pintype "passive"))
      (node (ref "C9") (pin "1") (pinfunction "1_1") (pintype "passive"))
      (node (ref "L1") (pin "2") (pinfunction "2_2") (pintype "passive"))
      (node (ref "U1") (pin "F6") (pinfunction "VDD_SOC_IN_1_F6") (pintype "passive"))
      (node (ref "U1") (pin "F7") (pinfunction "VDD_SOC_IN_2_F7") (pintype "passive"))
      (node (ref "U1") (pin "F8") (pinfunction "VDD_SOC_IN_3_F8") (pintype "passive"))
      (node (ref "U1") (pin "F9") (pinfunction "VDD_SOC_IN_4_F9") (pintype "passive"))
      (node (ref "U1") (pin "G6") (pinfunction "VDD_SOC_IN_5_G6") (pintype "passive"))
      (node (ref "U1") (pin "G9") (pinfunction "VDD_SOC_IN_6_G9") (pintype "passive"))
      (node (ref "U1") (pin "H6") (pinfunction "VDD_SOC_IN_7_H6") (pintype "passive"))
      (node (ref "U1") (pin "H9") (pinfunction "VDD_SOC_IN_8_H9") (pintype "passive"))
      (node (ref "U1") (pin "J5") (pinfunction "DCDC_SENSE_J5") (pintype "passive"))
      (node (ref "U1") (pin "J9") (pinfunction "VDD_SOC_IN_9_J9") (pintype "passive"))
    )
    (net (code "67") (name "/SX_RESET {slash} 3") (class "Default")
      (node (ref "U1") (pin "G5") (pinfunction "GPIO_EMC_05_G5") (pintype "passive"))
    )
    (net (code "68") (name "/TX1") (class "Default")
      (node (ref "U1") (pin "G11") (pinfunction "GPIO_AD_B0_03_G11") (pintype "passive"))
    )
    (net (code "69") (name "/TX2") (class "Default")
      (node (ref "U1") (pin "B11") (pinfunction "GPIO_B1_01_B11") (pintype "passive"))
    )
    (net (code "70") (name "/TX_CAM1 {slash} 15") (class "Default")
      (node (ref "U1") (pin "M12") (pinfunction "GPIO_AD_B1_03_M12") (pintype "passive"))
    )
    (net (code "71") (name "/TX_CAM2 {slash} 34") (class "Default")
      (node (ref "U1") (pin "D14") (pinfunction "GPIO_B1_13_D14") (pintype "passive"))
    )
    (net (code "72") (name "/XTAL0") (class "Default")
      (node (ref "C1") (pin "1") (pinfunction "1_1") (pintype "passive"))
      (node (ref "U1") (pin "N11") (pinfunction "XTALO_N11") (pintype "passive"))
      (node (ref "Y1") (pin "3") (pinfunction "X2_3") (pintype "passive"))
    )
    (net (code "73") (name "/XTAL1") (class "Default")
      (node (ref "C2") (pin "1") (pinfunction "1_1") (pintype "passive"))
      (node (ref "R1") (pin "1") (pinfunction "1_1") (pintype "passive"))
      (node (ref "U1") (pin "P11") (pinfunction "XTALI_P11") (pintype "passive"))
      (node (ref "Y1") (pin "1") (pinfunction "X1_1") (pintype "passive"))
    )
    (net (code "74") (name "GND") (class "Default")
      (node (ref "C1") (pin "2") (pinfunction "2_2") (pintype "passive"))
      (node (ref "C10") (pin "2") (pinfunction "2_2") (pintype "passive"))
      (node (ref "C11") (pin "2") (pinfunction "2_2") (pintype "passive"))
      (node (ref "C12") (pin "2") (pinfunction "2_2") (pintype "passive"))
      (node (ref "C13") (pin "2") (pinfunction "2_2") (pintype "passive"))
      (node (ref "C14") (pin "1") (pinfunction "1_1") (pintype "passive"))
      (node (ref "C15") (pin "1") (pinfunction "1_1") (pintype "passive"))
      (node (ref "C16") (pin "2") (pinfunction "2_2") (pintype "passive"))
      (node (ref "C17") (pin "2") (pinfunction "2_2") (pintype "passive"))
      (node (ref "C18") (pin "2") (pinfunction "2_2") (pintype "passive"))
      (node (ref "C19") (pin "2") (pinfunction "2_2") (pintype "passive"))
      (node (ref "C2") (pin "2") (pinfunction "2_2") (pintype "passive"))
      (node (ref "C20") (pin "2") (pinfunction "2_2") (pintype "passive"))
      (node (ref "C21") (pin "2") (pinfunction "2_2") (pintype "passive"))
      (node (ref "C22") (pin "2") (pinfunction "2_2") (pintype "passive"))
      (node (ref "C3") (pin "2") (pinfunction "2_2") (pintype "passive"))
      (node (ref "C4") (pin "1") (pinfunction "1_1") (pintype "passive"))
      (node (ref "C5") (pin "2") (pinfunction "2_2") (pintype "passive"))
      (node (ref "C6") (pin "2") (pinfunction "2_2") (pintype "passive"))
      (node (ref "C7") (pin "2") (pinfunction "2_2") (pintype "passive"))
      (node (ref "C8") (pin "2") (pinfunction "2_2") (pintype "passive"))
      (node (ref "C9") (pin "2") (pinfunction "2_2") (pintype "passive"))
      (node (ref "D4") (pin "2") (pinfunction "VSS_2") (pintype "passive"))
      (node (ref "D5") (pin "2") (pinfunction "VSS_2") (pintype "passive"))
      (node (ref "PB1") (pin "2") (pinfunction "2_2") (pintype "passive"))
      (node (ref "Q1") (pin "2") (pinfunction "E_2") (pintype "passive"))
      (node (ref "R1") (pin "2") (pinfunction "2_2") (pintype "passive"))
      (node (ref "R12") (pin "2") (pinfunction "2_2") (pintype "passive"))
      (node (ref "R3") (pin "2") (pinfunction "2_2") (pintype "passive"))
      (node (ref "R9") (pin "2") (pinfunction "2_2") (pintype "passive"))
      (node (ref "U1") (pin "A1") (pinfunction "VSS_1_A1") (pintype "passive"))
      (node (ref "U1") (pin "A14") (pinfunction "VSS_2_A14") (pintype "passive"))
      (node (ref "U1") (pin "B10") (pinfunction "VSS_4_B10") (pintype "passive"))
      (node (ref "U1") (pin "B5") (pinfunction "VSS_3_B5") (pintype "passive"))
      (node (ref "U1") (pin "E13") (pinfunction "VSS_6_E13") (pintype "passive"))
      (node (ref "U1") (pin "E2") (pinfunction "VSS_5_E2") (pintype "passive"))
      (node (ref "U1") (pin "G14") (pinfunction "GPIO_AD_B0_05_G14") (pintype "passive"))
      (node (ref "U1") (pin "G7") (pinfunction "VSS_7_G7") (pintype "passive"))
      (node (ref "U1") (pin "G8") (pinfunction "VSS_8_G8") (pintype "passive"))
      (node (ref "U1") (pin "H7") (pinfunction "VSS_9_H7") (pintype "passive"))
      (node (ref "U1") (pin "H8") (pinfunction "VSS_10_H8") (pintype "passive"))
      (node (ref "U1") (pin "J7") (pinfunction "VSS_11_J7") (pintype "passive"))
      (node (ref "U1") (pin "J8") (pinfunction "VSS_12_J8") (pintype "passive"))
      (node (ref "U1") (pin "K13") (pinfunction "VSS_14_K13") (pintype "passive"))
      (node (ref "U1") (pin "K2") (pinfunction "VSS_13_K2") (pintype "passive"))
      (node (ref "U1") (pin "K9") (pinfunction "NGND_KEL0_K9") (pintype "passive"))
      (node (ref "U1") (pin "L9") (pinfunction "VSS_15_L9") (pintype "passive"))
      (node (ref "U1") (pin "N1") (pinfunction "DCDC_GND_1_N1") (pintype "passive"))
      (node (ref "U1") (pin "N2") (pinfunction "DCDC_GND_2_N2") (pintype "passive"))
      (node (ref "U1") (pin "N5") (pinfunction "VSS_16_N5") (pintype "passive"))
      (node (ref "U1") (pin "N8") (pinfunction "VSS_17_N8") (pintype "passive"))
      (node (ref "U1") (pin "N9") (pinfunction "RTC_XTALI_N9") (pintype "passive"))
      (node (ref "U1") (pin "P1") (pinfunction "VSS_18_P1") (pintype "passive"))
      (node (ref "U1") (pin "P14") (pinfunction "VSS_19_P14") (pintype "passive"))
      (node (ref "U2") (pin "4") (pinfunction "GND_4") (pintype "passive"))
      (node (ref "U2") (pin "9") (pinfunction "EP_9") (pintype "passive"))
      (node (ref "U3") (pin "17") (pinfunction "EXP_17") (pintype "power_in"))
      (node (ref "U3") (pin "2") (pinfunction "VREFL/VSS_2") (pintype "power_in"))
      (node (ref "U4") (pin "5") (pinfunction "VSS_5") (pintype "passive"))
      (node (ref "Y1") (pin "2") (pinfunction "NC_2") (pintype "power_in"))
      (node (ref "Y1") (pin "4") (pinfunction "NC_4") (pintype "power_in"))
    )
    (net (code "75") (name "Net-(D1-PadK)") (class "Default")
      (node (ref "D1") (pin "K") (pinfunction "K_K") (pintype "passive"))
      (node (ref "R2") (pin "1") (pinfunction "1_1") (pintype "passive"))
    )
    (net (code "76") (name "Net-(D4-DOUT)") (class "Default")
      (node (ref "D4") (pin "1") (pinfunction "DOUT_1") (pintype "passive"))
      (node (ref "D5") (pin "4") (pinfunction "DIN_4") (pintype "passive"))
    )
    (net (code "77") (name "Net-(Q1-B)") (class "Default")
      (node (ref "Q1") (pin "1") (pinfunction "B_1") (pintype "passive"))
      (node (ref "R4") (pin "2") (pinfunction "2_2") (pintype "passive"))
    )
    (net (code "78") (name "Net-(Q1-C)") (class "Default")
      (node (ref "Buzzer1") (pin "N") (pinfunction "N_N") (pintype "passive"))
      (node (ref "Q1") (pin "3") (pinfunction "C_3") (pintype "passive"))
    )
    (net (code "79") (name "Net-(U1-DCDC_IN_1)") (class "Default")
      (node (ref "C11") (pin "1") (pinfunction "1_1") (pintype "passive"))
      (node (ref "C12") (pin "1") (pinfunction "1_1") (pintype "passive"))
      (node (ref "C13") (pin "1") (pinfunction "1_1") (pintype "passive"))
      (node (ref "L2") (pin "1") (pinfunction "1_1") (pintype "passive"))
      (node (ref "U1") (pin "L1") (pinfunction "DCDC_IN_1_L1") (pintype "passive"))
      (node (ref "U1") (pin "L2") (pinfunction "DCDC_IN_2_L2") (pintype "passive"))
    )
    (net (code "80") (name "Net-(U1-NVCC_PLL)") (class "Default")
      (node (ref "C18") (pin "1") (pinfunction "1_1") (pintype "passive"))
      (node (ref "C19") (pin "1") (pinfunction "1_1") (pintype "passive"))
      (node (ref "U1") (pin "P10") (pinfunction "NVCC_PLL_P10") (pintype "passive"))
    )
    (net (code "81") (name "Net-(U1-VDD_HIGH_CAP)") (class "Default")
      (node (ref "C20") (pin "1") (pinfunction "1_1") (pintype "passive"))
      (node (ref "C21") (pin "1") (pinfunction "1_1") (pintype "passive"))
      (node (ref "U1") (pin "P8") (pinfunction "VDD_HIGH_CAP_P8") (pintype "passive"))
    )
    (net (code "82") (name "Net-(U1-VDD_SNVS_CAP)") (class "Default")
      (node (ref "C16") (pin "1") (pinfunction "1_1") (pintype "passive"))
      (node (ref "U1") (pin "M10") (pinfunction "VDD_SNVS_CAP_M10") (pintype "passive"))
    )
    (net (code "83") (name "Net-(U1-VDD_USB_CAP)") (class "Default")
      (node (ref "C5") (pin "1") (pinfunction "1_1") (pintype "passive"))
      (node (ref "C6") (pin "1") (pinfunction "1_1") (pintype "passive"))
      (node (ref "D3") (pin "A") (pinfunction "A_A") (pintype "passive"))
      (node (ref "U1") (pin "K8") (pinfunction "VDD_USB_CAP_K8") (pintype "passive"))
    )
    (net (code "84") (name "Net-(U3-PTB2{slash}IRQ_7)") (class "Default")
      (node (ref "PB1") (pin "1") (pinfunction "1_1") (pintype "passive"))
      (node (ref "U3") (pin "10") (pinfunction "PTB2/IRQ_7_10") (pintype "bidirectional"))
    )
    (net (code "85") (name "Net-(U3-PTB3{slash}IRQ_10)") (class "Default")
      (node (ref "R2") (pin "2") (pinfunction "2_2") (pintype "passive"))
      (node (ref "U3") (pin "11") (pinfunction "PTB3/IRQ_10_11") (pintype "bidirectional"))
    )
    (net (code "86") (name "unconnected-(D5-DOUT-Pad1)") (class "Default")
      (node (ref "D5") (pin "1") (pinfunction "DOUT_1") (pintype "passive"))
    )
    (net (code "87") (name "unconnected-(U1-CCM_CLK1_N-PadP13)") (class "Default")
      (node (ref "U1") (pin "P13") (pinfunction "CCM_CLK1_N_P13") (pintype "passive"))
    )
    (net (code "88") (name "unconnected-(U1-CCM_CLK1_P-PadN13)") (class "Default")
      (node (ref "U1") (pin "N13") (pinfunction "CCM_CLK1_P_N13") (pintype "passive"))
    )
    (net (code "89") (name "unconnected-(U1-GPANAIO-PadN10)") (class "Default")
      (node (ref "U1") (pin "N10") (pinfunction "GPANAIO_N10") (pintype "passive"))
    )
    (net (code "90") (name "unconnected-(U1-GPIO_AD_B0_00-PadM14)") (class "Default")
      (node (ref "U1") (pin "M14") (pinfunction "GPIO_AD_B0_00_M14") (pintype "passive"))
    )
    (net (code "91") (name "unconnected-(U1-GPIO_AD_B0_01-PadH10)") (class "Default")
      (node (ref "U1") (pin "H10") (pinfunction "GPIO_AD_B0_01_H10") (pintype "passive"))
    )
    (net (code "92") (name "unconnected-(U1-GPIO_AD_B0_14-PadH14)") (class "Default")
      (node (ref "U1") (pin "H14") (pinfunction "GPIO_AD_B0_14_H14") (pintype "passive"))
    )
    (net (code "93") (name "unconnected-(U1-GPIO_AD_B0_15-PadL10)") (class "Default")
      (node (ref "U1") (pin "L10") (pinfunction "GPIO_AD_B0_15_L10") (pintype "passive"))
    )
    (net (code "94") (name "unconnected-(U1-GPIO_AD_B1_05-PadK12)") (class "Default")
      (node (ref "U1") (pin "K12") (pinfunction "GPIO_AD_B1_05_K12") (pintype "passive"))
    )
    (net (code "95") (name "unconnected-(U1-GPIO_AD_B1_07-PadK10)") (class "Default")
      (node (ref "U1") (pin "K10") (pinfunction "GPIO_AD_B1_07_K10") (pintype "passive"))
    )
    (net (code "96") (name "unconnected-(U1-GPIO_AD_B1_12-PadH12)") (class "Default")
      (node (ref "U1") (pin "H12") (pinfunction "GPIO_AD_B1_12_H12") (pintype "passive"))
    )
    (net (code "97") (name "unconnected-(U1-GPIO_AD_B1_13-PadH11)") (class "Default")
      (node (ref "U1") (pin "H11") (pinfunction "GPIO_AD_B1_13_H11") (pintype "passive"))
    )
    (net (code "98") (name "unconnected-(U1-GPIO_AD_B1_14-PadG12)") (class "Default")
      (node (ref "U1") (pin "G12") (pinfunction "GPIO_AD_B1_14_G12") (pintype "passive"))
    )
    (net (code "99") (name "unconnected-(U1-GPIO_B0_04-PadC8)") (class "Default")
      (node (ref "U1") (pin "C8") (pinfunction "GPIO_B0_04_C8") (pintype "passive"))
    )
    (net (code "100") (name "unconnected-(U1-GPIO_B0_05-PadB8)") (class "Default")
      (node (ref "U1") (pin "B8") (pinfunction "GPIO_B0_05_B8") (pintype "passive"))
    )
    (net (code "101") (name "unconnected-(U1-GPIO_B0_06-PadA8)") (class "Default")
      (node (ref "U1") (pin "A8") (pinfunction "GPIO_B0_06_A8") (pintype "passive"))
    )
    (net (code "102") (name "unconnected-(U1-GPIO_B0_07-PadA9)") (class "Default")
      (node (ref "U1") (pin "A9") (pinfunction "GPIO_B0_07_A9") (pintype "passive"))
    )
    (net (code "103") (name "unconnected-(U1-GPIO_B0_08-PadB9)") (class "Default")
      (node (ref "U1") (pin "B9") (pinfunction "GPIO_B0_08_B9") (pintype "passive"))
    )
    (net (code "104") (name "unconnected-(U1-GPIO_B0_09-PadC9)") (class "Default")
      (node (ref "U1") (pin "C9") (pinfunction "GPIO_B0_09_C9") (pintype "passive"))
    )
    (net (code "105") (name "unconnected-(U1-GPIO_B0_14-PadE10)") (class "Default")
      (node (ref "U1") (pin "E10") (pinfunction "GPIO_B0_14_E10") (pintype "passive"))
    )
    (net (code "106") (name "unconnected-(U1-GPIO_B0_15-PadE11)") (class "Default")
      (node (ref "U1") (pin "E11") (pinfunction "GPIO_B0_15_E11") (pintype "passive"))
    )
    (net (code "107") (name "unconnected-(U1-GPIO_B1_03-PadD11)") (class "Default")
      (node (ref "U1") (pin "D11") (pinfunction "GPIO_B1_03_D11") (pintype "passive"))
    )
    (net (code "108") (name "unconnected-(U1-GPIO_B1_04-PadE12)") (class "Default")
      (node (ref "U1") (pin "E12") (pinfunction "GPIO_B1_04_E12") (pintype "passive"))
    )
    (net (code "109") (name "unconnected-(U1-GPIO_B1_05-PadD12)") (class "Default")
      (node (ref "U1") (pin "D12") (pinfunction "GPIO_B1_05_D12") (pintype "passive"))
    )
    (net (code "110") (name "unconnected-(U1-GPIO_B1_06-PadC12)") (class "Default")
      (node (ref "U1") (pin "C12") (pinfunction "GPIO_B1_06_C12") (pintype "passive"))
    )
    (net (code "111") (name "unconnected-(U1-GPIO_B1_07-PadB12)") (class "Default")
      (node (ref "U1") (pin "B12") (pinfunction "GPIO_B1_07_B12") (pintype "passive"))
    )
    (net (code "112") (name "unconnected-(U1-GPIO_B1_08-PadA12)") (class "Default")
      (node (ref "U1") (pin "A12") (pinfunction "GPIO_B1_08_A12") (pintype "passive"))
    )
    (net (code "113") (name "unconnected-(U1-GPIO_B1_09-PadA13)") (class "Default")
      (node (ref "U1") (pin "A13") (pinfunction "GPIO_B1_09_A13") (pintype "passive"))
    )
    (net (code "114") (name "unconnected-(U1-GPIO_B1_10-PadB13)") (class "Default")
      (node (ref "U1") (pin "B13") (pinfunction "GPIO_B1_10_B13") (pintype "passive"))
    )
    (net (code "115") (name "unconnected-(U1-GPIO_B1_11-PadC13)") (class "Default")
      (node (ref "U1") (pin "C13") (pinfunction "GPIO_B1_11_C13") (pintype "passive"))
    )
    (net (code "116") (name "unconnected-(U1-GPIO_B1_14-PadC14)") (class "Default")
      (node (ref "U1") (pin "C14") (pinfunction "GPIO_B1_14_C14") (pintype "passive"))
    )
    (net (code "117") (name "unconnected-(U1-GPIO_B1_15-PadB14)") (class "Default")
      (node (ref "U1") (pin "B14") (pinfunction "GPIO_B1_15_B14") (pintype "passive"))
    )
    (net (code "118") (name "unconnected-(U1-GPIO_EMC_00-PadE3)") (class "Default")
      (node (ref "U1") (pin "E3") (pinfunction "GPIO_EMC_00_E3") (pintype "passive"))
    )
    (net (code "119") (name "unconnected-(U1-GPIO_EMC_02-PadF4)") (class "Default")
      (node (ref "U1") (pin "F4") (pinfunction "GPIO_EMC_02_F4") (pintype "passive"))
    )
    (net (code "120") (name "unconnected-(U1-GPIO_EMC_03-PadG4)") (class "Default")
      (node (ref "U1") (pin "G4") (pinfunction "GPIO_EMC_03_G4") (pintype "passive"))
    )
    (net (code "121") (name "unconnected-(U1-GPIO_EMC_06-PadH5)") (class "Default")
      (node (ref "U1") (pin "H5") (pinfunction "GPIO_EMC_06_H5") (pintype "passive"))
    )
    (net (code "122") (name "unconnected-(U1-GPIO_EMC_09-PadC2)") (class "Default")
      (node (ref "U1") (pin "C2") (pinfunction "GPIO_EMC_09_C2") (pintype "passive"))
    )
    (net (code "123") (name "unconnected-(U1-GPIO_EMC_10-PadG1)") (class "Default")
      (node (ref "U1") (pin "G1") (pinfunction "GPIO_EMC_10_G1") (pintype "passive"))
    )
    (net (code "124") (name "unconnected-(U1-GPIO_EMC_11-PadG3)") (class "Default")
      (node (ref "U1") (pin "G3") (pinfunction "GPIO_EMC_11_G3") (pintype "passive"))
    )
    (net (code "125") (name "unconnected-(U1-GPIO_EMC_12-PadH1)") (class "Default")
      (node (ref "U1") (pin "H1") (pinfunction "GPIO_EMC_12_H1") (pintype "passive"))
    )
    (net (code "126") (name "unconnected-(U1-GPIO_EMC_13-PadA6)") (class "Default")
      (node (ref "U1") (pin "A6") (pinfunction "GPIO_EMC_13_A6") (pintype "passive"))
    )
    (net (code "127") (name "unconnected-(U1-GPIO_EMC_14-PadB6)") (class "Default")
      (node (ref "U1") (pin "B6") (pinfunction "GPIO_EMC_14_B6") (pintype "passive"))
    )
    (net (code "128") (name "unconnected-(U1-GPIO_EMC_15-PadB1)") (class "Default")
      (node (ref "U1") (pin "B1") (pinfunction "GPIO_EMC_15_B1") (pintype "passive"))
    )
    (net (code "129") (name "unconnected-(U1-GPIO_EMC_16-PadA5)") (class "Default")
      (node (ref "U1") (pin "A5") (pinfunction "GPIO_EMC_16_A5") (pintype "passive"))
    )
    (net (code "130") (name "unconnected-(U1-GPIO_EMC_17-PadA4)") (class "Default")
      (node (ref "U1") (pin "A4") (pinfunction "GPIO_EMC_17_A4") (pintype "passive"))
    )
    (net (code "131") (name "unconnected-(U1-GPIO_EMC_18-PadB2)") (class "Default")
      (node (ref "U1") (pin "B2") (pinfunction "GPIO_EMC_18_B2") (pintype "passive"))
    )
    (net (code "132") (name "unconnected-(U1-GPIO_EMC_19-PadB4)") (class "Default")
      (node (ref "U1") (pin "B4") (pinfunction "GPIO_EMC_19_B4") (pintype "passive"))
    )
    (net (code "133") (name "unconnected-(U1-GPIO_EMC_20-PadA3)") (class "Default")
      (node (ref "U1") (pin "A3") (pinfunction "GPIO_EMC_20_A3") (pintype "passive"))
    )
    (net (code "134") (name "unconnected-(U1-GPIO_EMC_21-PadC1)") (class "Default")
      (node (ref "U1") (pin "C1") (pinfunction "GPIO_EMC_21_C1") (pintype "passive"))
    )
    (net (code "135") (name "unconnected-(U1-GPIO_EMC_22-PadF1)") (class "Default")
      (node (ref "U1") (pin "F1") (pinfunction "GPIO_EMC_22_F1") (pintype "passive"))
    )
    (net (code "136") (name "unconnected-(U1-GPIO_EMC_23-PadG2)") (class "Default")
      (node (ref "U1") (pin "G2") (pinfunction "GPIO_EMC_23_G2") (pintype "passive"))
    )
    (net (code "137") (name "unconnected-(U1-GPIO_EMC_24-PadD3)") (class "Default")
      (node (ref "U1") (pin "D3") (pinfunction "GPIO_EMC_24_D3") (pintype "passive"))
    )
    (net (code "138") (name "unconnected-(U1-GPIO_EMC_25-PadD2)") (class "Default")
      (node (ref "U1") (pin "D2") (pinfunction "GPIO_EMC_25_D2") (pintype "passive"))
    )
    (net (code "139") (name "unconnected-(U1-GPIO_EMC_26-PadB3)") (class "Default")
      (node (ref "U1") (pin "B3") (pinfunction "GPIO_EMC_26_B3") (pintype "passive"))
    )
    (net (code "140") (name "unconnected-(U1-GPIO_EMC_27-PadA2)") (class "Default")
      (node (ref "U1") (pin "A2") (pinfunction "GPIO_EMC_27_A2") (pintype "passive"))
    )
    (net (code "141") (name "unconnected-(U1-GPIO_EMC_28-PadD1)") (class "Default")
      (node (ref "U1") (pin "D1") (pinfunction "GPIO_EMC_28_D1") (pintype "passive"))
    )
    (net (code "142") (name "unconnected-(U1-GPIO_EMC_29-PadE1)") (class "Default")
      (node (ref "U1") (pin "E1") (pinfunction "GPIO_EMC_29_E1") (pintype "passive"))
    )
    (net (code "143") (name "unconnected-(U1-GPIO_EMC_30-PadC6)") (class "Default")
      (node (ref "U1") (pin "C6") (pinfunction "GPIO_EMC_30_C6") (pintype "passive"))
    )
    (net (code "144") (name "unconnected-(U1-GPIO_EMC_33-PadC4)") (class "Default")
      (node (ref "U1") (pin "C4") (pinfunction "GPIO_EMC_33_C4") (pintype "passive"))
    )
    (net (code "145") (name "unconnected-(U1-GPIO_EMC_34-PadD4)") (class "Default")
      (node (ref "U1") (pin "D4") (pinfunction "GPIO_EMC_34_D4") (pintype "passive"))
    )
    (net (code "146") (name "unconnected-(U1-GPIO_EMC_35-PadE5)") (class "Default")
      (node (ref "U1") (pin "E5") (pinfunction "GPIO_EMC_35_E5") (pintype "passive"))
    )
    (net (code "147") (name "unconnected-(U1-GPIO_EMC_38-PadD6)") (class "Default")
      (node (ref "U1") (pin "D6") (pinfunction "GPIO_EMC_38_D6") (pintype "passive"))
    )
    (net (code "148") (name "unconnected-(U1-GPIO_EMC_39-PadB7)") (class "Default")
      (node (ref "U1") (pin "B7") (pinfunction "GPIO_EMC_39_B7") (pintype "passive"))
    )
    (net (code "149") (name "unconnected-(U1-GPIO_EMC_40-PadA7)") (class "Default")
      (node (ref "U1") (pin "A7") (pinfunction "GPIO_EMC_40_A7") (pintype "passive"))
    )
    (net (code "150") (name "unconnected-(U1-GPIO_EMC_41-PadC7)") (class "Default")
      (node (ref "U1") (pin "C7") (pinfunction "GPIO_EMC_41_C7") (pintype "passive"))
    )
    (net (code "151") (name "unconnected-(U1-GPIO_SD_B1_00-PadL5)") (class "Default")
      (node (ref "U1") (pin "L5") (pinfunction "GPIO_SD_B1_00_L5") (pintype "passive"))
    )
    (net (code "152") (name "unconnected-(U1-GPIO_SD_B1_01-PadM5)") (class "Default")
      (node (ref "U1") (pin "M5") (pinfunction "GPIO_SD_B1_01_M5") (pintype "passive"))
    )
    (net (code "153") (name "unconnected-(U1-GPIO_SD_B1_02-PadM3)") (class "Default")
      (node (ref "U1") (pin "M3") (pinfunction "GPIO_SD_B1_02_M3") (pintype "passive"))
    )
    (net (code "154") (name "unconnected-(U1-GPIO_SD_B1_03-PadM4)") (class "Default")
      (node (ref "U1") (pin "M4") (pinfunction "GPIO_SD_B1_03_M4") (pintype "passive"))
    )
    (net (code "155") (name "unconnected-(U1-GPIO_SD_B1_04-PadP2)") (class "Default")
      (node (ref "U1") (pin "P2") (pinfunction "GPIO_SD_B1_04_P2") (pintype "passive"))
    )
    (net (code "156") (name "unconnected-(U1-GPIO_SD_B1_05-PadN3)") (class "Default")
      (node (ref "U1") (pin "N3") (pinfunction "GPIO_SD_B1_05_N3") (pintype "passive"))
    )
    (net (code "157") (name "unconnected-(U1-ONOFF-PadM6)") (class "Default")
      (node (ref "U1") (pin "M6") (pinfunction "ONOFF_M6") (pintype "passive"))
    )
    (net (code "158") (name "unconnected-(U1-PMIC_STBY_REQ-PadL7)") (class "Default")
      (node (ref "U1") (pin "L7") (pinfunction "PMIC_STBY_REQ_L7") (pintype "passive"))
    )
    (net (code "159") (name "unconnected-(U1-RTC_XTALO-PadP9)") (class "Default")
      (node (ref "U1") (pin "P9") (pinfunction "RTC_XTALO_P9") (pintype "passive"))
    )
    (net (code "160") (name "unconnected-(U1-TEST_MODE-PadK6)") (class "Default")
      (node (ref "U1") (pin "K6") (pinfunction "TEST_MODE_K6") (pintype "passive"))
    )
    (net (code "161") (name "unconnected-(U1-USB_OTG1_CHD_B-PadN12)") (class "Default")
      (node (ref "U1") (pin "N12") (pinfunction "USB_OTG1_CHD_B_N12") (pintype "passive"))
    )
    (net (code "162") (name "unconnected-(U1-USB_OTG2_DN-PadN7)") (class "Default")
      (node (ref "U1") (pin "N7") (pinfunction "USB_OTG2_DN_N7") (pintype "passive"))
    )
    (net (code "163") (name "unconnected-(U1-USB_OTG2_DP-PadP7)") (class "Default")
      (node (ref "U1") (pin "P7") (pinfunction "USB_OTG2_DP_P7") (pintype "passive"))
    )
    (net (code "164") (name "unconnected-(U1-WAKEUP-PadL6)") (class "Default")
      (node (ref "U1") (pin "L6") (pinfunction "WAKEUP_L6") (pintype "passive"))
    )
    (net (code "165") (name "unconnected-(U3-PTA0{slash}IRQ_0-Pad14)") (class "Default")
      (node (ref "U3") (pin "14") (pinfunction "PTA0/IRQ_0_14") (pintype "bidirectional+no_connect"))
    )
    (net (code "166") (name "unconnected-(U3-PTA2-Pad16)") (class "Default")
      (node (ref "U3") (pin "16") (pinfunction "PTA2_16") (pintype "bidirectional+no_connect"))
    )
  )
)
